# MPU6000.net
KiCad netlist of a schematic drawn in Altium Designer
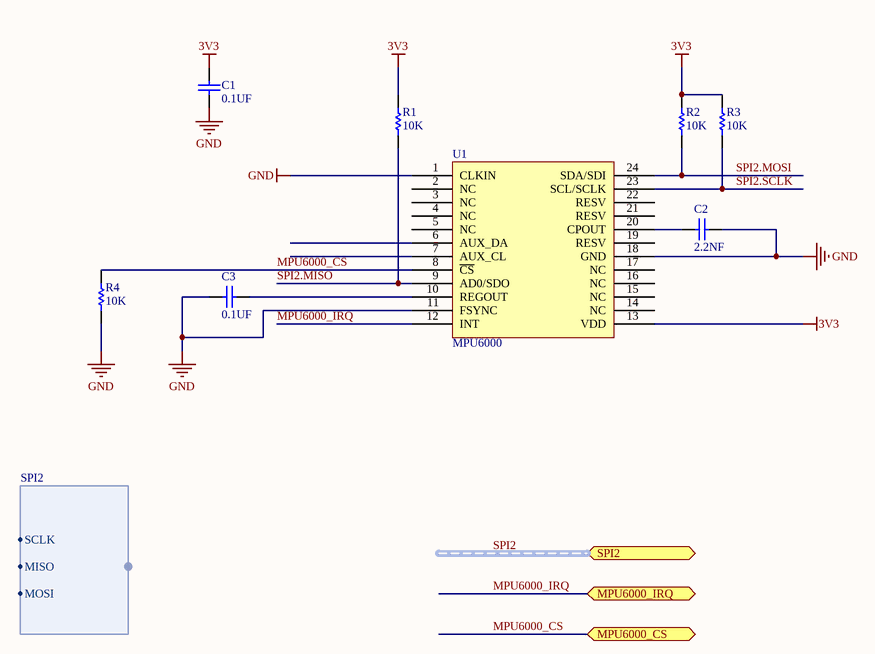
[diagram p0: MPU6000.SchDoc]

(export (version "E")
  (design (tool "Eeschema 10.0.6"))
  (components
    (comp (ref "C1")
      (value "0.1UF")
      (footprint "RC0805")
      (description "Capacitor")
      (fields (field (name "Comment") "Cap") (field (name "PUBLISHER") "Altium Limited"))
      (libsource (lib "Miscellaneous Devices") (part "Cap"))
    )
    (comp (ref "C2")
      (value "2.2NF")
      (footprint "RC0805")
      (description "Capacitor")
      (fields (field (name "Comment") "Cap") (field (name "PUBLISHER") "Altium Limited"))
      (libsource (lib "Miscellaneous Devices") (part "Cap"))
    )
    (comp (ref "C3")
      (value "0.1UF")
      (footprint "RC0805")
      (description "Capacitor")
      (fields (field (name "Comment") "Cap") (field (name "PUBLISHER") "Altium Limited"))
      (libsource (lib "Miscellaneous Devices") (part "Cap"))
    )
    (comp (ref "R1")
      (value "10K")
      (footprint "RC0805")
      (description "Resistor")
      (fields (field (name "Comment") "Res1") (field (name "PUBLISHER") "Altium Limited"))
      (libsource (lib "Miscellaneous Devices") (part "Res1"))
    )
    (comp (ref "R2")
      (value "10K")
      (footprint "RC0805")
      (description "Resistor")
      (fields (field (name "Comment") "Res1") (field (name "PUBLISHER") "Altium Limited"))
      (libsource (lib "Miscellaneous Devices") (part "Res1"))
    )
    (comp (ref "R3")
      (value "10K")
      (footprint "RC0805")
      (description "Resistor")
      (fields (field (name "Comment") "Res1") (field (name "PUBLISHER") "Altium Limited"))
      (libsource (lib "Miscellaneous Devices") (part "Res1"))
    )
    (comp (ref "R4")
      (value "10K")
      (footprint "RC0805")
      (description "Resistor")
      (fields (field (name "Comment") "Res1") (field (name "PUBLISHER") "Altium Limited"))
      (libsource (lib "Miscellaneous Devices") (part "Res1"))
    )
    (comp (ref "U1") (value "MPU6000") (footprint "QFN24_M") (libsource (lib "MPU6000") (part "MPU6000")))
  )
  (nets
    (net (code "2") (name "/MPU6000_CS") (class "Default")
      (node (ref "R4") (pin "1") (pinfunction "1_1") (pintype "passive"))
      (node (ref "U1") (pin "8") (pinfunction "~{CS}_8") (pintype "passive"))
    )
    (net (code "3") (name "/MPU6000_IRQ") (class "Default")
      (node (ref "U1") (pin "12") (pinfunction "INT_12") (pintype "passive"))
    )
    (net (code "4") (name "/SPI2.MISO") (class "Default")
      (node (ref "R1") (pin "2") (pinfunction "2_2") (pintype "passive"))
      (node (ref "U1") (pin "9") (pinfunction "AD0/SDO_9") (pintype "passive"))
    )
    (net (code "5") (name "/SPI2.MOSI") (class "Default")
      (node (ref "R2") (pin "2") (pinfunction "2_2") (pintype "passive"))
      (node (ref "U1") (pin "24") (pinfunction "SDA/SDI_24") (pintype "passive"))
    )
    (net (code "6") (name "/SPI2.SCLK") (class "Default")
      (node (ref "R3") (pin "2") (pinfunction "2_2") (pintype "passive"))
      (node (ref "U1") (pin "23") (pinfunction "SCL/SCLK_23") (pintype "passive"))
    )
    (net (code "8") (name "3V3") (class "Default")
      (node (ref "C1") (pin "2") (pinfunction "2_2") (pintype "passive"))
      (node (ref "R1") (pin "1") (pinfunction "1_1") (pintype "passive"))
      (node (ref "R2") (pin "1") (pinfunction "1_1") (pintype "passive"))
      (node (ref "R3") (pin "1") (pinfunction "1_1") (pintype "passive"))
      (node (ref "U1") (pin "13") (pinfunction "VDD_13") (pintype "passive"))
    )
    (net (code "9") (name "GND") (class "Default")
      (node (ref "C1") (pin "1") (pinfunction "1_1") (pintype "passive"))
      (node (ref "C2") (pin "2") (pinfunction "2_2") (pintype "passive"))
      (node (ref "C3") (pin "1") (pinfunction "1_1") (pintype "passive"))
      (node (ref "R4") (pin "2") (pinfunction "2_2") (pintype "passive"))
      (node (ref "U1") (pin "1") (pinfunction "CLKIN_1") (pintype "passive"))
      (node (ref "U1") (pin "11") (pinfunction "FSYNC_11") (pintype "passive"))
      (node (ref "U1") (pin "18") (pinfunction "GND_18") (pintype "passive"))
    )
    (net (code "10") (name "Net-(U1-CPOUT)") (class "Default")
      (node (ref "C2") (pin "1") (pinfunction "1_1") (pintype "passive"))
      (node (ref "U1") (pin "20") (pinfunction "CPOUT_20") (pintype "passive"))
    )
    (net (code "11") (name "Net-(U1-REGOUT)") (class "Default")
      (node (ref "C3") (pin "2") (pinfunction "2_2") (pintype "passive"))
      (node (ref "U1") (pin "10") (pinfunction "REGOUT_10") (pintype "passive"))
    )
    (net (code "12") (name "unconnected-(U1-AUX_CL-Pad7)") (class "Default")
      (node (ref "U1") (pin "7") (pinfunction "AUX_CL_7") (pintype "passive"))
    )
    (net (code "13") (name "unconnected-(U1-AUX_DA-Pad6)") (class "Default")
      (node (ref "U1") (pin "6") (pinfunction "AUX_DA_6") (pintype "passive"))
    )
    (net (code "14") (name "unconnected-(U1-NC-Pad2)") (class "Default")
      (node (ref "U1") (pin "2") (pinfunction "NC_2") (pintype "passive"))
    )
    (net (code "15") (name "unconnected-(U1-NC-Pad3)") (class "Default")
      (node (ref "U1") (pin "3") (pinfunction "NC_3") (pintype "passive"))
    )
    (net (code "16") (name "unconnected-(U1-NC-Pad4)") (class "Default")
      (node (ref "U1") (pin "4") (pinfunction "NC_4") (pintype "passive"))
    )
    (net (code "17") (name "unconnected-(U1-NC-Pad5)") (class "Default")
      (node (ref "U1") (pin "5") (pinfunction "NC_5") (pintype "passive"))
    )
    (net (code "18") (name "unconnected-(U1-NC-Pad14)") (class "Default")
      (node (ref "U1") (pin "14") (pinfunction "NC_14") (pintype "passive"))
    )
    (net (code "19") (name "unconnected-(U1-NC-Pad15)") (class "Default")
      (node (ref "U1") (pin "15") (pinfunction "NC_15") (pintype "passive"))
    )
    (net (code "20") (name "unconnected-(U1-NC-Pad16)") (class "Default")
      (node (ref "U1") (pin "16") (pinfunction "NC_16") (pintype "passive"))
    )
    (net (code "21") (name "unconnected-(U1-NC-Pad17)") (class "Default")
      (node (ref "U1") (pin "17") (pinfunction "NC_17") (pintype "passive"))
    )
    (net (code "22") (name "unconnected-(U1-RESV-Pad19)") (class "Default")
      (node (ref "U1") (pin "19") (pinfunction "RESV_19") (pintype "passive"))
    )
    (net (code "23") (name "unconnected-(U1-RESV-Pad21)") (class "Default")
      (node (ref "U1") (pin "21") (pinfunction "RESV_21") (pintype "passive"))
    )
    (net (code "24") (name "unconnected-(U1-RESV-Pad22)") (class "Default")
      (node (ref "U1") (pin "22") (pinfunction "RESV_22") (pintype "passive"))
    )
  )
)
